# Nebula.net
KiCad netlist of a schematic drawn in Altium Designer
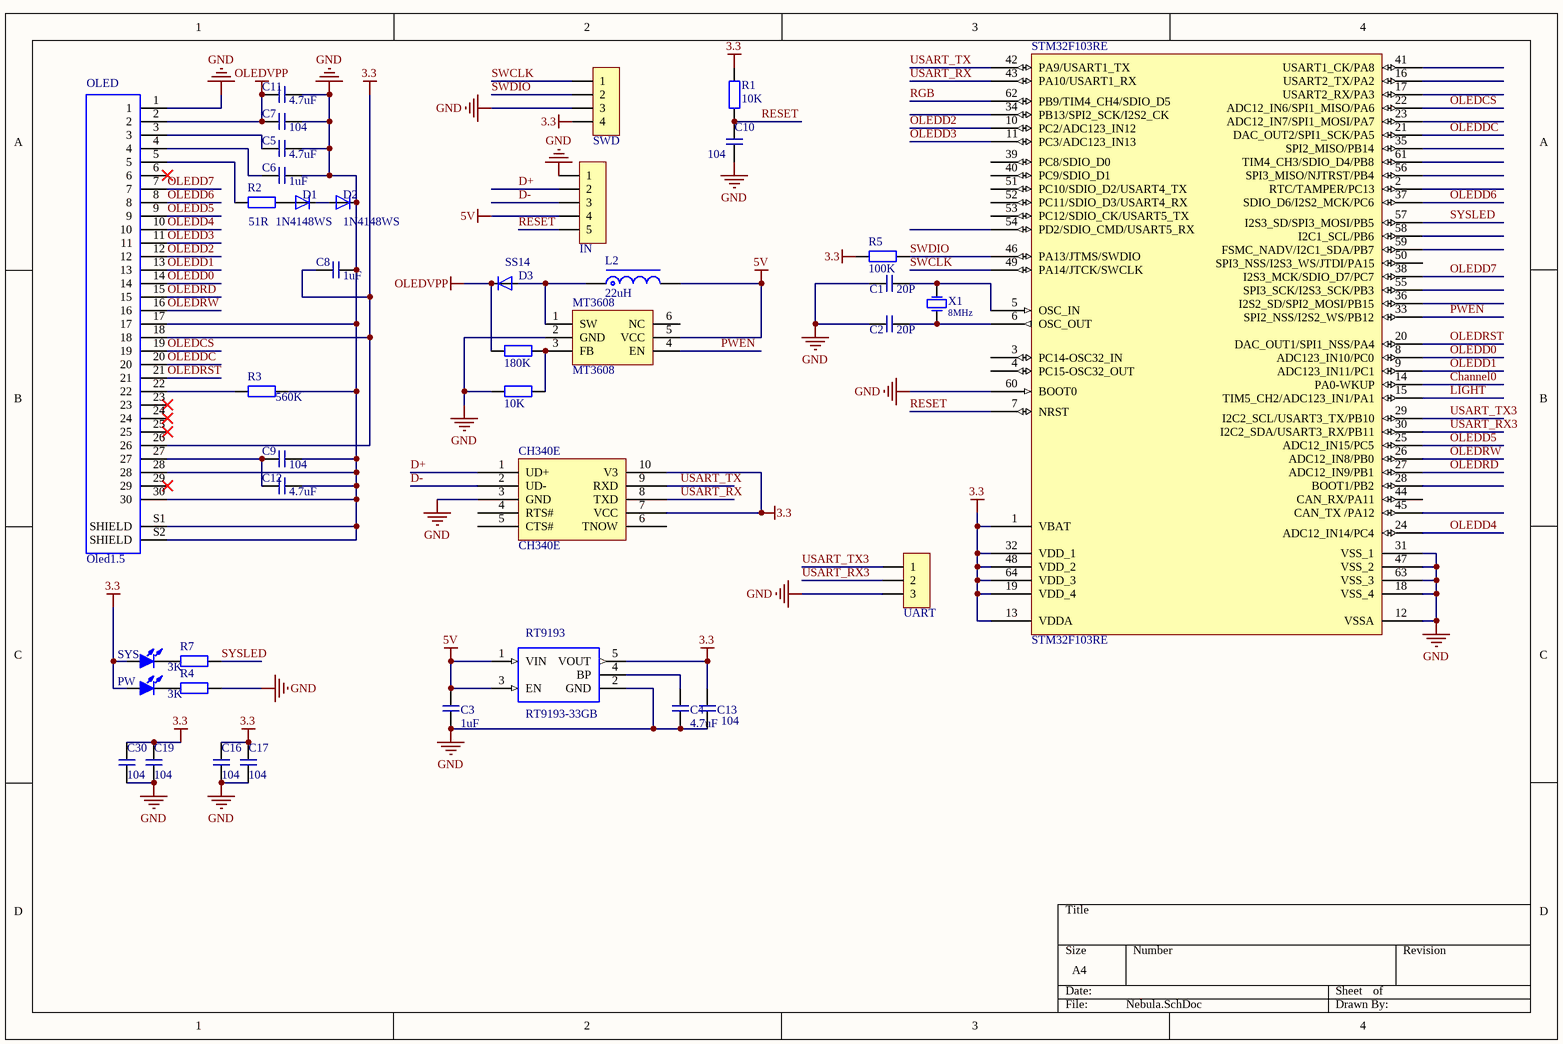
[diagram p0: Nebula.SchDoc]

(export (version "E")
  (design (tool "Eeschema 10.0.6"))
  (components
    (comp (ref "C1") (value "20P") (footprint "0603C") (libsource (lib "Schlib1") (part "电容")))
    (comp (ref "C2") (value "20P") (footprint "0603C") (libsource (lib "Schlib1") (part "电容")))
    (comp (ref "C3") (value "1uF") (footprint "0603C") (libsource (lib "Schlib1") (part "电容")))
    (comp (ref "C4") (value "4.7uF") (footprint "0603C") (libsource (lib "Schlib1") (part "电容")))
    (comp (ref "C5") (value "4.7uF") (footprint "0603C") (libsource (lib "Schlib1") (part "电容")))
    (comp (ref "C6") (value "1uF") (footprint "0603C") (libsource (lib "Schlib1") (part "电容")))
    (comp (ref "C7") (value "104") (footprint "0603C") (libsource (lib "Schlib1") (part "电容")))
    (comp (ref "C8") (value "1uF") (footprint "0603C") (libsource (lib "Schlib1") (part "电容")))
    (comp (ref "C9") (value "104") (footprint "0603C") (libsource (lib "Schlib1") (part "电容")))
    (comp (ref "C10") (value "104") (footprint "0603C") (libsource (lib "Schlib1") (part "电容")))
    (comp (ref "C11") (value "4.7uF") (footprint "0603C") (libsource (lib "Schlib1") (part "电容")))
    (comp (ref "C12") (value "4.7uF") (footprint "0603C") (libsource (lib "Schlib1") (part "电容")))
    (comp (ref "C13") (value "104") (footprint "0603C") (libsource (lib "Schlib1") (part "电容")))
    (comp (ref "C16") (value "104") (footprint "0603C") (libsource (lib "Schlib1") (part "电容")))
    (comp (ref "C17") (value "104") (footprint "0603C") (libsource (lib "Schlib1") (part "电容")))
    (comp (ref "C19") (value "104") (footprint "0603C") (libsource (lib "Schlib1") (part "电容")))
    (comp (ref "C30") (value "104") (footprint "0603C") (libsource (lib "Schlib1") (part "电容")))
    (comp (ref "CH340E") (value "CH340E") (footprint "MSOP10_L") (libsource (lib "CUBE_T1") (part "CH340E")))
    (comp (ref "D1")
      (value "1N4148WS")
      (footprint "SOD323_1N4148WS")
      (description "Diode Switching 75V 0.3A 2-Pin SOD-323 T/R")
      (fields (field (name "MF") "ON Semiconductor"))
      (libsource (lib "1N4148WS") (part "1N4148WS"))
    )
    (comp (ref "D2")
      (value "1N4148WS")
      (footprint "SOD323_1N4148WS")
      (description "Diode Switching 75V 0.3A 2-Pin SOD-323 T/R")
      (fields (field (name "MF") "ON Semiconductor"))
      (libsource (lib "1N4148WS") (part "1N4148WS"))
    )
    (comp (ref "D3")
      (value "SS14")
      (footprint "SOD323_1N4148WS")
      (description "Diode Switching 75V 0.3A 2-Pin SOD-323 T/R")
      (fields (field (name "MF") "ON Semiconductor") (field (name "MP") "1N4148WS"))
      (libsource (lib "1N4148WS") (part "1N4148WS"))
    )
    (comp (ref "IN")
      (value "HDR-1X5")
      (footprint "ZH1.5-LS-5P")
      (description "5P接插件")
      (fields (field (name "版权归属") "源创客"))
      (libsource (lib "4.3   - 接插件-脚距1.5") (part "Header 5"))
    )
    (comp (ref "L2")
      (value "22uH")
      (footprint "1210-ec")
      (description "功率屏蔽电感")
      (fields (field (name "版权归属") "源创客"))
      (libsource (lib "3.1   - 电阻-电容-电感") (part "L-CDRH"))
    )
    (comp (ref "MT3608")
      (value "MT3608")
      (footprint "SOT23-6N")
      (description "可调升压芯片")
      (fields (field (name "版权归属") "源创客"))
      (libsource (lib "1.3   - 电源类芯片") (part "SX1308"))
    )
    (comp (ref "OLED")
      (value "Oled1.5")
      (footprint "PCBComponent_1")
      (description "FH12 Series 30 Position 0.5 mm Pitch Surface Mount Right Angle Flip Lock FFC/FPC")
      (fields (field (name "MF") "Hirose Electric") (field (name "MP") "FH12-30S-0.5SH_55_"))
      (libsource (lib "Nebula") (part "FH12-30S-0.5SH(55)"))
    )
    (comp (ref "PW")
      (value "白色")
      (footprint "0603LED")
      (description "方形LED")
      (fields (field (name "版权归属") "源创客"))
      (libsource (lib "9.1   - LED") (part "LED-F234"))
    )
    (comp (ref "R1")
      (value "10K")
      (footprint "0603R")
      (description "贴片电阻")
      (fields (field (name "版权归属") "源创客"))
      (libsource (lib "3.1   - 电阻-电容-电感") (part "R"))
    )
    (comp (ref "R2")
      (value "51R")
      (footprint "0603R")
      (description "贴片电阻")
      (fields (field (name "版权归属") "源创客"))
      (libsource (lib "3.1   - 电阻-电容-电感") (part "R"))
    )
    (comp (ref "R3")
      (value "560K")
      (footprint "0603R")
      (description "贴片电阻")
      (fields (field (name "版权归属") "源创客"))
      (libsource (lib "3.1   - 电阻-电容-电感") (part "R"))
    )
    (comp (ref "R4")
      (value "3K")
      (footprint "0603R")
      (description "贴片电阻")
      (fields (field (name "版权归属") "源创客"))
      (libsource (lib "3.1   - 电阻-电容-电感") (part "R"))
    )
    (comp (ref "R5")
      (value "100K")
      (footprint "0603R")
      (description "贴片电阻")
      (fields (field (name "版权归属") "源创客"))
      (libsource (lib "3.1   - 电阻-电容-电感") (part "R"))
    )
    (comp (ref "R7")
      (value "3K")
      (footprint "0603R")
      (description "贴片电阻")
      (fields (field (name "版权归属") "源创客"))
      (libsource (lib "3.1   - 电阻-电容-电感") (part "R"))
    )
    (comp (ref "RB")
      (value "180K")
      (footprint "0603R")
      (description "贴片电阻")
      (fields (field (name "版权归属") "源创客"))
      (libsource (lib "3.1   - 电阻-电容-电感") (part "R"))
    )
    (comp (ref "RS")
      (value "10K")
      (footprint "0603R")
      (description "贴片电阻")
      (fields (field (name "版权归属") "源创客"))
      (libsource (lib "3.1   - 电阻-电容-电感") (part "R"))
    )
    (comp (ref "RT9193")
      (value "RT9193-33GB")
      (footprint "sot23-5")
      (description "RT9193 Series 300 mA 3.3 V Ultra-Low Noise Ultra-Fast CMOS LDO Regulator-SC-70-5")
      (fields (field (name "MF") "Richtek USA"))
      (libsource (lib "RT9193-33GB") (part "RT9193-33GB"))
    )
    (comp (ref "STM32F103RE")
      (value "STM32F103RE")
      (footprint "LQFP64 10X10_N")
      (description "32位STM单片机")
      (fields (field (name "版权归属") "源创客"))
      (libsource (lib "2.1   - STM32系列单片机") (part "STM32F103RE"))
    )
    (comp (ref "SWD")
      (value "HDR-1X4")
      (footprint "ZH1.5-LS-4P")
      (description "4P接插件")
      (fields (field (name "版权归属") "源创客"))
      (libsource (lib "4.3   - 接插件-脚距1.5") (part "Header 4"))
    )
    (comp (ref "SYS")
      (value "粉色")
      (footprint "0603LED")
      (description "方形LED")
      (fields (field (name "版权归属") "源创客"))
      (libsource (lib "9.1   - LED") (part "LED-F234"))
    )
    (comp (ref "UART")
      (value "HDR-1X3")
      (footprint "ZH1.5-LS-3P")
      (description "3P接插件")
      (fields (field (name "版权归属") "源创客"))
      (libsource (lib "4.3   - 接插件-脚距1.5") (part "Header 3"))
    )
    (comp (ref "X1")
      (value "8MHz")
      (footprint "OSC 5032-2P")
      (description "XTAL,8MHz,±20PPM,12.6*4.5")
      (fields (field (name "Comment") "1.6.1.01.005.001"))
      (libsource (lib "Mark_7") (part "1.6.1.01.005.001"))
    )
  )
  (nets
    (net (code "1") (name "/Channel0") (class "Default")
      (node (ref "STM32F103RE") (pin "14") (pinfunction "PA0-WKUP_14") (pintype "bidirectional"))
    )
    (net (code "2") (name "/D+") (class "Default")
      (node (ref "CH340E") (pin "1") (pinfunction "UD+_1") (pintype "passive"))
      (node (ref "IN") (pin "2") (pinfunction "2_2") (pintype "passive"))
    )
    (net (code "3") (name "/D-") (class "Default")
      (node (ref "CH340E") (pin "2") (pinfunction "UD-_2") (pintype "passive"))
      (node (ref "IN") (pin "3") (pinfunction "3_3") (pintype "passive"))
    )
    (net (code "4") (name "/LIGHT") (class "Default")
      (node (ref "STM32F103RE") (pin "15") (pinfunction "TIM5_CH2/ADC123_IN1/PA1_15") (pintype "bidirectional"))
    )
    (net (code "5") (name "/OLEDCS") (class "Default")
      (node (ref "OLED") (pin "19") (pinfunction "19_19") (pintype "passive"))
      (node (ref "STM32F103RE") (pin "22") (pinfunction "ADC12_IN6/SPI1_MISO/PA6_22") (pintype "bidirectional"))
    )
    (net (code "6") (name "/OLEDD0") (class "Default")
      (node (ref "OLED") (pin "14") (pinfunction "14_14") (pintype "passive"))
      (node (ref "STM32F103RE") (pin "8") (pinfunction "ADC123_IN10/PC0_8") (pintype "bidirectional"))
    )
    (net (code "7") (name "/OLEDD1") (class "Default")
      (node (ref "OLED") (pin "13") (pinfunction "13_13") (pintype "passive"))
      (node (ref "STM32F103RE") (pin "9") (pinfunction "ADC123_IN11/PC1_9") (pintype "bidirectional"))
    )
    (net (code "8") (name "/OLEDD2") (class "Default")
      (node (ref "OLED") (pin "12") (pinfunction "12_12") (pintype "passive"))
      (node (ref "STM32F103RE") (pin "10") (pinfunction "PC2/ADC123_IN12_10") (pintype "bidirectional"))
    )
    (net (code "9") (name "/OLEDD3") (class "Default")
      (node (ref "OLED") (pin "11") (pinfunction "11_11") (pintype "passive"))
      (node (ref "STM32F103RE") (pin "11") (pinfunction "PC3/ADC123_IN13_11") (pintype "bidirectional"))
    )
    (net (code "10") (name "/OLEDD4") (class "Default")
      (node (ref "OLED") (pin "10") (pinfunction "10_10") (pintype "passive"))
      (node (ref "STM32F103RE") (pin "24") (pinfunction "ADC12_IN14/PC4_24") (pintype "bidirectional"))
    )
    (net (code "11") (name "/OLEDD5") (class "Default")
      (node (ref "OLED") (pin "9") (pinfunction "9_9") (pintype "passive"))
      (node (ref "STM32F103RE") (pin "25") (pinfunction "ADC12_IN15/PC5_25") (pintype "bidirectional"))
    )
    (net (code "12") (name "/OLEDD6") (class "Default")
      (node (ref "OLED") (pin "8") (pinfunction "8_8") (pintype "passive"))
      (node (ref "STM32F103RE") (pin "37") (pinfunction "SDIO_D6/I2S2_MCK/PC6_37") (pintype "bidirectional"))
    )
    (net (code "13") (name "/OLEDD7") (class "Default")
      (node (ref "OLED") (pin "7") (pinfunction "7_7") (pintype "passive"))
      (node (ref "STM32F103RE") (pin "38") (pinfunction "I2S3_MCK/SDIO_D7/PC7_38") (pintype "bidirectional"))
    )
    (net (code "14") (name "/OLEDDC") (class "Default")
      (node (ref "OLED") (pin "20") (pinfunction "20_20") (pintype "passive"))
      (node (ref "STM32F103RE") (pin "21") (pinfunction "DAC_OUT2/SPI1_SCK/PA5_21") (pintype "bidirectional"))
    )
    (net (code "15") (name "/OLEDRD") (class "Default")
      (node (ref "OLED") (pin "15") (pinfunction "15_15") (pintype "passive"))
      (node (ref "STM32F103RE") (pin "27") (pinfunction "ADC12_IN9/PB1_27") (pintype "bidirectional"))
    )
    (net (code "16") (name "/OLEDRST") (class "Default")
      (node (ref "OLED") (pin "21") (pinfunction "21_21") (pintype "passive"))
      (node (ref "STM32F103RE") (pin "20") (pinfunction "DAC_OUT1/SPI1_NSS/PA4_20") (pintype "bidirectional"))
    )
    (net (code "17") (name "/OLEDRW") (class "Default")
      (node (ref "OLED") (pin "16") (pinfunction "16_16") (pintype "passive"))
      (node (ref "STM32F103RE") (pin "26") (pinfunction "ADC12_IN8/PB0_26") (pintype "bidirectional"))
    )
    (net (code "18") (name "/PWEN") (class "Default")
      (node (ref "MT3608") (pin "4") (pinfunction "EN_4") (pintype "passive"))
      (node (ref "STM32F103RE") (pin "33") (pinfunction "SPI2_NSS/I2S2_WS/PB12_33") (pintype "bidirectional"))
    )
    (net (code "19") (name "/RESET") (class "Default")
      (node (ref "C10") (pin "1") (pinfunction "1_1") (pintype "passive"))
      (node (ref "IN") (pin "5") (pinfunction "5_5") (pintype "passive"))
      (node (ref "R1") (pin "2") (pinfunction "2_2") (pintype "passive"))
      (node (ref "STM32F103RE") (pin "7") (pinfunction "NRST_7") (pintype "bidirectional"))
    )
    (net (code "20") (name "/RGB") (class "Default")
      (node (ref "STM32F103RE") (pin "62") (pinfunction "PB9/TIM4_CH4/SDIO_D5_62") (pintype "bidirectional"))
    )
    (net (code "21") (name "/SWCLK") (class "Default")
      (node (ref "STM32F103RE") (pin "49") (pinfunction "PA14/JTCK/SWCLK_49") (pintype "bidirectional"))
      (node (ref "SWD") (pin "1") (pinfunction "1_1") (pintype "passive"))
    )
    (net (code "22") (name "/SWDIO") (class "Default")
      (node (ref "R5") (pin "2") (pinfunction "2_2") (pintype "passive"))
      (node (ref "STM32F103RE") (pin "46") (pinfunction "PA13/JTMS/SWDIO_46") (pintype "bidirectional"))
      (node (ref "SWD") (pin "2") (pinfunction "2_2") (pintype "passive"))
    )
    (net (code "23") (name "/SYSLED") (class "Default")
      (node (ref "R7") (pin "1") (pinfunction "1_1") (pintype "passive"))
      (node (ref "STM32F103RE") (pin "57") (pinfunction "I2S3_SD/SPI3_MOSI/PB5_57") (pintype "bidirectional"))
    )
    (net (code "24") (name "/USART_RX") (class "Default")
      (node (ref "CH340E") (pin "8") (pinfunction "TXD_8") (pintype "passive"))
      (node (ref "STM32F103RE") (pin "43") (pinfunction "PA10/USART1_RX_43") (pintype "bidirectional"))
    )
    (net (code "25") (name "/USART_RX3") (class "Default")
      (node (ref "STM32F103RE") (pin "30") (pinfunction "I2C2_SDA/USART3_RX/PB11_30") (pintype "bidirectional"))
      (node (ref "UART") (pin "2") (pinfunction "2_2") (pintype "passive"))
    )
    (net (code "26") (name "/USART_TX") (class "Default")
      (node (ref "CH340E") (pin "9") (pinfunction "RXD_9") (pintype "passive"))
      (node (ref "STM32F103RE") (pin "42") (pinfunction "PA9/USART1_TX_42") (pintype "bidirectional"))
    )
    (net (code "27") (name "/USART_TX3") (class "Default")
      (node (ref "STM32F103RE") (pin "29") (pinfunction "I2C2_SCL/USART3_TX/PB10_29") (pintype "bidirectional"))
      (node (ref "UART") (pin "1") (pinfunction "1_1") (pintype "passive"))
    )
    (net (code "28") (name "3.3") (class "Default")
      (node (ref "C13") (pin "2") (pinfunction "2_2") (pintype "passive"))
      (node (ref "C16") (pin "1") (pinfunction "1_1") (pintype "passive"))
      (node (ref "C17") (pin "1") (pinfunction "1_1") (pintype "passive"))
      (node (ref "C19") (pin "1") (pinfunction "1_1") (pintype "passive"))
      (node (ref "C30") (pin "1") (pinfunction "1_1") (pintype "passive"))
      (node (ref "C8") (pin "1") (pinfunction "1_1") (pintype "passive"))
      (node (ref "CH340E") (pin "10") (pinfunction "V3_10") (pintype "passive"))
      (node (ref "CH340E") (pin "7") (pinfunction "VCC_7") (pintype "passive"))
      (node (ref "OLED") (pin "18") (pinfunction "18_18") (pintype "passive"))
      (node (ref "OLED") (pin "26") (pinfunction "26_26") (pintype "passive"))
      (node (ref "PW") (pin "1") (pinfunction "A_1") (pintype "passive"))
      (node (ref "R1") (pin "1") (pinfunction "1_1") (pintype "passive"))
      (node (ref "R5") (pin "1") (pinfunction "1_1") (pintype "passive"))
      (node (ref "RT9193") (pin "5") (pinfunction "VOUT_5") (pintype "output"))
      (node (ref "STM32F103RE") (pin "1") (pinfunction "VBAT_1") (pintype "power_in"))
      (node (ref "STM32F103RE") (pin "13") (pinfunction "VDDA_13") (pintype "power_in"))
      (node (ref "STM32F103RE") (pin "19") (pinfunction "VDD_4_19") (pintype "power_in"))
      (node (ref "STM32F103RE") (pin "32") (pinfunction "VDD_1_32") (pintype "power_in"))
      (node (ref "STM32F103RE") (pin "48") (pinfunction "VDD_2_48") (pintype "power_in"))
      (node (ref "STM32F103RE") (pin "64") (pinfunction "VDD_3_64") (pintype "power_in"))
      (node (ref "SWD") (pin "4") (pinfunction "4_4") (pintype "passive"))
      (node (ref "SYS") (pin "1") (pinfunction "A_1") (pintype "passive"))
    )
    (net (code "29") (name "5V") (class "Default")
      (node (ref "C3") (pin "2") (pinfunction "2_2") (pintype "passive"))
      (node (ref "IN") (pin "4") (pinfunction "4_4") (pintype "passive"))
      (node (ref "L2") (pin "2") (pinfunction "2_2") (pintype "passive"))
      (node (ref "MT3608") (pin "5") (pinfunction "VCC_5") (pintype "passive"))
      (node (ref "RT9193") (pin "1") (pinfunction "VIN_1") (pintype "input"))
      (node (ref "RT9193") (pin "3") (pinfunction "EN_3") (pintype "input"))
    )
    (net (code "30") (name "GND") (class "Default")
      (node (ref "C1") (pin "1") (pinfunction "1_1") (pintype "passive"))
      (node (ref "C10") (pin "2") (pinfunction "2_2") (pintype "passive"))
      (node (ref "C11") (pin "2") (pinfunction "2_2") (pintype "passive"))
      (node (ref "C12") (pin "2") (pinfunction "2_2") (pintype "passive"))
      (node (ref "C13") (pin "1") (pinfunction "1_1") (pintype "passive"))
      (node (ref "C16") (pin "2") (pinfunction "2_2") (pintype "passive"))
      (node (ref "C17") (pin "2") (pinfunction "2_2") (pintype "passive"))
      (node (ref "C19") (pin "2") (pinfunction "2_2") (pintype "passive"))
      (node (ref "C2") (pin "1") (pinfunction "1_1") (pintype "passive"))
      (node (ref "C3") (pin "1") (pinfunction "1_1") (pintype "passive"))
      (node (ref "C30") (pin "2") (pinfunction "2_2") (pintype "passive"))
      (node (ref "C4") (pin "1") (pinfunction "1_1") (pintype "passive"))
      (node (ref "C5") (pin "2") (pinfunction "2_2") (pintype "passive"))
      (node (ref "C6") (pin "2") (pinfunction "2_2") (pintype "passive"))
      (node (ref "C7") (pin "2") (pinfunction "2_2") (pintype "passive"))
      (node (ref "C8") (pin "2") (pinfunction "2_2") (pintype "passive"))
      (node (ref "C9") (pin "2") (pinfunction "2_2") (pintype "passive"))
      (node (ref "CH340E") (pin "3") (pinfunction "GND_3") (pintype "passive"))
      (node (ref "D2") (pin "C") (pinfunction "C_C") (pintype "passive"))
      (node (ref "IN") (pin "1") (pinfunction "1_1") (pintype "passive"))
      (node (ref "MT3608") (pin "2") (pinfunction "GND_2") (pintype "passive"))
      (node (ref "OLED") (pin "1") (pinfunction "1_1") (pintype "passive"))
      (node (ref "OLED") (pin "17") (pinfunction "17_17") (pintype "passive"))
      (node (ref "OLED") (pin "28") (pinfunction "28_28") (pintype "passive"))
      (node (ref "OLED") (pin "30") (pinfunction "30_30") (pintype "passive"))
      (node (ref "OLED") (pin "S1") (pinfunction "SHIELD_S1") (pintype "passive"))
      (node (ref "OLED") (pin "S2") (pinfunction "SHIELD_S2") (pintype "passive"))
      (node (ref "R3") (pin "1") (pinfunction "1_1") (pintype "passive"))
      (node (ref "R4") (pin "1") (pinfunction "1_1") (pintype "passive"))
      (node (ref "RS") (pin "1") (pinfunction "1_1") (pintype "passive"))
      (node (ref "RT9193") (pin "2") (pinfunction "GND_2") (pintype "power_in"))
      (node (ref "STM32F103RE") (pin "12") (pinfunction "VSSA_12") (pintype "power_in"))
      (node (ref "STM32F103RE") (pin "18") (pinfunction "VSS_4_18") (pintype "power_in"))
      (node (ref "STM32F103RE") (pin "31") (pinfunction "VSS_1_31") (pintype "passive"))
      (node (ref "STM32F103RE") (pin "47") (pinfunction "VSS_2_47") (pintype "passive"))
      (node (ref "STM32F103RE") (pin "60") (pinfunction "BOOT0_60") (pintype "input"))
      (node (ref "STM32F103RE") (pin "63") (pinfunction "VSS_3_63") (pintype "power_in"))
      (node (ref "SWD") (pin "3") (pinfunction "3_3") (pintype "passive"))
      (node (ref "UART") (pin "3") (pinfunction "3_3") (pintype "passive"))
    )
    (net (code "31") (name "Net-(C5-Pad1)") (class "Default")
      (node (ref "C5") (pin "1") (pinfunction "1_1") (pintype "passive"))
      (node (ref "OLED") (pin "3") (pinfunction "3_3") (pintype "passive"))
    )
    (net (code "32") (name "Net-(C6-Pad1)") (class "Default")
      (node (ref "C6") (pin "1") (pinfunction "1_1") (pintype "passive"))
      (node (ref "OLED") (pin "4") (pinfunction "4_4") (pintype "passive"))
    )
    (net (code "33") (name "Net-(C12-Pad1)") (class "Default")
      (node (ref "C12") (pin "1") (pinfunction "1_1") (pintype "passive"))
      (node (ref "C9") (pin "1") (pinfunction "1_1") (pintype "passive"))
      (node (ref "OLED") (pin "27") (pinfunction "27_27") (pintype "passive"))
    )
    (net (code "34") (name "Net-(D1-PadA)") (class "Default")
      (node (ref "D1") (pin "A") (pinfunction "A_A") (pintype "passive"))
      (node (ref "R2") (pin "1") (pinfunction "1_1") (pintype "passive"))
    )
    (net (code "35") (name "Net-(D1-PadC)") (class "Default")
      (node (ref "D1") (pin "C") (pinfunction "C_C") (pintype "passive"))
      (node (ref "D2") (pin "A") (pinfunction "A_A") (pintype "passive"))
    )
    (net (code "36") (name "Net-(MT3608-FB)") (class "Default")
      (node (ref "MT3608") (pin "3") (pinfunction "FB_3") (pintype "passive"))
      (node (ref "RB") (pin "2") (pinfunction "2_2") (pintype "passive"))
      (node (ref "RS") (pin "2") (pinfunction "2_2") (pintype "passive"))
    )
    (net (code "37") (name "Net-(MT3608-SW)") (class "Default")
      (node (ref "D3") (pin "A") (pinfunction "A_A") (pintype "passive"))
      (node (ref "L2") (pin "1") (pinfunction "1_1") (pintype "passive"))
      (node (ref "MT3608") (pin "1") (pinfunction "SW_1") (pintype "passive"))
    )
    (net (code "38") (name "Net-(OLED-Pad5)") (class "Default")
      (node (ref "OLED") (pin "5") (pinfunction "5_5") (pintype "passive"))
      (node (ref "R2") (pin "2") (pinfunction "2_2") (pintype "passive"))
    )
    (net (code "39") (name "Net-(OLED-Pad22)") (class "Default")
      (node (ref "OLED") (pin "22") (pinfunction "22_22") (pintype "passive"))
      (node (ref "R3") (pin "2") (pinfunction "2_2") (pintype "passive"))
    )
    (net (code "40") (name "Net-(PW-K)") (class "Default")
      (node (ref "PW") (pin "2") (pinfunction "K_2") (pintype "passive"))
      (node (ref "R4") (pin "2") (pinfunction "2_2") (pintype "passive"))
    )
    (net (code "41") (name "Net-(RT9193-BP)") (class "Default")
      (node (ref "C4") (pin "2") (pinfunction "2_2") (pintype "passive"))
      (node (ref "RT9193") (pin "4") (pinfunction "BP_4") (pintype "passive"))
    )
    (net (code "42") (name "Net-(STM32F103RE-OSC_IN)") (class "Default")
      (node (ref "C1") (pin "2") (pinfunction "2_2") (pintype "passive"))
      (node (ref "STM32F103RE") (pin "5") (pinfunction "OSC_IN_5") (pintype "input"))
      (node (ref "X1") (pin "2") (pinfunction "OSC2_2") (pintype "passive"))
    )
    (net (code "43") (name "Net-(STM32F103RE-OSC_OUT)") (class "Default")
      (node (ref "C2") (pin "2") (pinfunction "2_2") (pintype "passive"))
      (node (ref "STM32F103RE") (pin "6") (pinfunction "OSC_OUT_6") (pintype "output"))
      (node (ref "X1") (pin "1") (pinfunction "OSC1_1") (pintype "passive"))
    )
    (net (code "44") (name "Net-(SYS-K)") (class "Default")
      (node (ref "R7") (pin "2") (pinfunction "2_2") (pintype "passive"))
      (node (ref "SYS") (pin "2") (pinfunction "K_2") (pintype "passive"))
    )
    (net (code "45") (name "OLEDVPP") (class "Default")
      (node (ref "C11") (pin "1") (pinfunction "1_1") (pintype "passive"))
      (node (ref "C7") (pin "1") (pinfunction "1_1") (pintype "passive"))
      (node (ref "D3") (pin "C") (pinfunction "C_C") (pintype "passive"))
      (node (ref "OLED") (pin "2") (pinfunction "2_2") (pintype "passive"))
      (node (ref "RB") (pin "1") (pinfunction "1_1") (pintype "passive"))
    )
    (net (code "46") (name "unconnected-(CH340E-CTS#-Pad5)") (class "Default")
      (node (ref "CH340E") (pin "5") (pinfunction "CTS#_5") (pintype "passive"))
    )
    (net (code "47") (name "unconnected-(CH340E-RTS#-Pad4)") (class "Default")
      (node (ref "CH340E") (pin "4") (pinfunction "RTS#_4") (pintype "passive"))
    )
    (net (code "48") (name "unconnected-(CH340E-TNOW-Pad6)") (class "Default")
      (node (ref "CH340E") (pin "6") (pinfunction "TNOW_6") (pintype "passive"))
    )
    (net (code "49") (name "unconnected-(MT3608-NC-Pad6)") (class "Default")
      (node (ref "MT3608") (pin "6") (pinfunction "NC_6") (pintype "passive"))
    )
    (net (code "50") (name "unconnected-(OLED-Pad6)") (class "Default")
      (node (ref "OLED") (pin "6") (pinfunction "6_6") (pintype "passive+no_connect"))
    )
    (net (code "51") (name "unconnected-(OLED-Pad23)") (class "Default")
      (node (ref "OLED") (pin "23") (pinfunction "23_23") (pintype "passive+no_connect"))
    )
    (net (code "52") (name "unconnected-(OLED-Pad24)") (class "Default")
      (node (ref "OLED") (pin "24") (pinfunction "24_24") (pintype "passive+no_connect"))
    )
    (net (code "53") (name "unconnected-(OLED-Pad25)") (class "Default")
      (node (ref "OLED") (pin "25") (pinfunction "25_25") (pintype "passive+no_connect"))
    )
    (net (code "54") (name "unconnected-(OLED-Pad29)") (class "Default")
      (node (ref "OLED") (pin "29") (pinfunction "29_29") (pintype "passive+no_connect"))
    )
    (net (code "55") (name "unconnected-(STM32F103RE-ADC12_IN7{slash}SPI1_MOSI{slash}PA7-Pad23)") (class "Default")
      (node (ref "STM32F103RE") (pin "23") (pinfunction "ADC12_IN7/SPI1_MOSI/PA7_23") (pintype "bidirectional"))
    )
    (net (code "56") (name "unconnected-(STM32F103RE-BOOT1{slash}PB2-Pad28)") (class "Default")
      (node (ref "STM32F103RE") (pin "28") (pinfunction "BOOT1/PB2_28") (pintype "bidirectional"))
    )
    (net (code "57") (name "unconnected-(STM32F103RE-CAN_RX{slash}PA11-Pad44)") (class "Default")
      (node (ref "STM32F103RE") (pin "44") (pinfunction "CAN_RX/PA11_44") (pintype "bidirectional"))
    )
    (net (code "58") (name "unconnected-(STM32F103RE-CAN_TX_{slash}PA12-Pad45)") (class "Default")
      (node (ref "STM32F103RE") (pin "45") (pinfunction "CAN_TX_/PA12_45") (pintype "bidirectional"))
    )
    (net (code "59") (name "unconnected-(STM32F103RE-FSMC_NADV{slash}I2C1_SDA{slash}PB7-Pad59)") (class "Default")
      (node (ref "STM32F103RE") (pin "59") (pinfunction "FSMC_NADV/I2C1_SDA/PB7_59") (pintype "bidirectional"))
    )
    (net (code "60") (name "unconnected-(STM32F103RE-I2C1_SCL{slash}PB6-Pad58)") (class "Default")
      (node (ref "STM32F103RE") (pin "58") (pinfunction "I2C1_SCL/PB6_58") (pintype "bidirectional"))
    )
    (net (code "61") (name "unconnected-(STM32F103RE-I2S2_SD{slash}SPI2_MOSI{slash}PB15-Pad36)") (class "Default")
      (node (ref "STM32F103RE") (pin "36") (pinfunction "I2S2_SD/SPI2_MOSI/PB15_36") (pintype "bidirectional"))
    )
    (net (code "62") (name "unconnected-(STM32F103RE-PB13{slash}SPI2_SCK{slash}I2S2_CK-Pad34)") (class "Default")
      (node (ref "STM32F103RE") (pin "34") (pinfunction "PB13/SPI2_SCK/I2S2_CK_34") (pintype "bidirectional"))
    )
    (net (code "63") (name "unconnected-(STM32F103RE-PC8{slash}SDIO_D0-Pad39)") (class "Default")
      (node (ref "STM32F103RE") (pin "39") (pinfunction "PC8/SDIO_D0_39") (pintype "bidirectional"))
    )
    (net (code "64") (name "unconnected-(STM32F103RE-PC9{slash}SDIO_D1-Pad40)") (class "Default")
      (node (ref "STM32F103RE") (pin "40") (pinfunction "PC9/SDIO_D1_40") (pintype "bidirectional"))
    )
    (net (code "65") (name "unconnected-(STM32F103RE-PC10{slash}SDIO_D2{slash}USART4_TX-Pad51)") (class "Default")
      (node (ref "STM32F103RE") (pin "51") (pinfunction "PC10/SDIO_D2/USART4_TX_51") (pintype "bidirectional"))
    )
    (net (code "66") (name "unconnected-(STM32F103RE-PC11{slash}SDIO_D3{slash}USART4_RX-Pad52)") (class "Default")
      (node (ref "STM32F103RE") (pin "52") (pinfunction "PC11/SDIO_D3/USART4_RX_52") (pintype "bidirectional"))
    )
    (net (code "67") (name "unconnected-(STM32F103RE-PC12{slash}SDIO_CK{slash}USART5_TX-Pad53)") (class "Default")
      (node (ref "STM32F103RE") (pin "53") (pinfunction "PC12/SDIO_CK/USART5_TX_53") (pintype "bidirectional"))
    )
    (net (code "68") (name "unconnected-(STM32F103RE-PC14-OSC32_IN-Pad3)") (class "Default")
      (node (ref "STM32F103RE") (pin "3") (pinfunction "PC14-OSC32_IN_3") (pintype "bidirectional"))
    )
    (net (code "69") (name "unconnected-(STM32F103RE-PC15-OSC32_OUT-Pad4)") (class "Default")
      (node (ref "STM32F103RE") (pin "4") (pinfunction "PC15-OSC32_OUT_4") (pintype "bidirectional"))
    )
    (net (code "70") (name "unconnected-(STM32F103RE-PD2{slash}SDIO_CMD{slash}USART5_RX-Pad54)") (class "Default")
      (node (ref "STM32F103RE") (pin "54") (pinfunction "PD2/SDIO_CMD/USART5_RX_54") (pintype "bidirectional"))
    )
    (net (code "71") (name "unconnected-(STM32F103RE-RTC{slash}TAMPER{slash}PC13-Pad2)") (class "Default")
      (node (ref "STM32F103RE") (pin "2") (pinfunction "RTC/TAMPER/PC13_2") (pintype "bidirectional"))
    )
    (net (code "72") (name "unconnected-(STM32F103RE-SPI2_MISO{slash}PB14-Pad35)") (class "Default")
      (node (ref "STM32F103RE") (pin "35") (pinfunction "SPI2_MISO/PB14_35") (pintype "bidirectional"))
    )
    (net (code "73") (name "unconnected-(STM32F103RE-SPI3_MISO{slash}NJTRST{slash}PB4-Pad56)") (class "Default")
      (node (ref "STM32F103RE") (pin "56") (pinfunction "SPI3_MISO/NJTRST/PB4_56") (pintype "bidirectional"))
    )
    (net (code "74") (name "unconnected-(STM32F103RE-SPI3_NSS{slash}I2S3_WS{slash}JTDI{slash}PA15-Pad50)") (class "Default")
      (node (ref "STM32F103RE") (pin "50") (pinfunction "SPI3_NSS/I2S3_WS/JTDI/PA15_50") (pintype "bidirectional"))
    )
    (net (code "75") (name "unconnected-(STM32F103RE-SPI3_SCK{slash}I2S3_SCK{slash}PB3-Pad55)") (class "Default")
      (node (ref "STM32F103RE") (pin "55") (pinfunction "SPI3_SCK/I2S3_SCK/PB3_55") (pintype "bidirectional"))
    )
    (net (code "76") (name "unconnected-(STM32F103RE-TIM4_CH3{slash}SDIO_D4{slash}PB8-Pad61)") (class "Default")
      (node (ref "STM32F103RE") (pin "61") (pinfunction "TIM4_CH3/SDIO_D4/PB8_61") (pintype "bidirectional"))
    )
    (net (code "77") (name "unconnected-(STM32F103RE-USART1_CK{slash}PA8-Pad41)") (class "Default")
      (node (ref "STM32F103RE") (pin "41") (pinfunction "USART1_CK/PA8_41") (pintype "bidirectional"))
    )
    (net (code "78") (name "unconnected-(STM32F103RE-USART2_RX{slash}PA3-Pad17)") (class "Default")
      (node (ref "STM32F103RE") (pin "17") (pinfunction "USART2_RX/PA3_17") (pintype "bidirectional"))
    )
    (net (code "79") (name "unconnected-(STM32F103RE-USART2_TX{slash}PA2-Pad16)") (class "Default")
      (node (ref "STM32F103RE") (pin "16") (pinfunction "USART2_TX/PA2_16") (pintype "bidirectional"))
    )
  )
)
